# AT91.net
KiCad netlist of a schematic drawn in Altium Designer
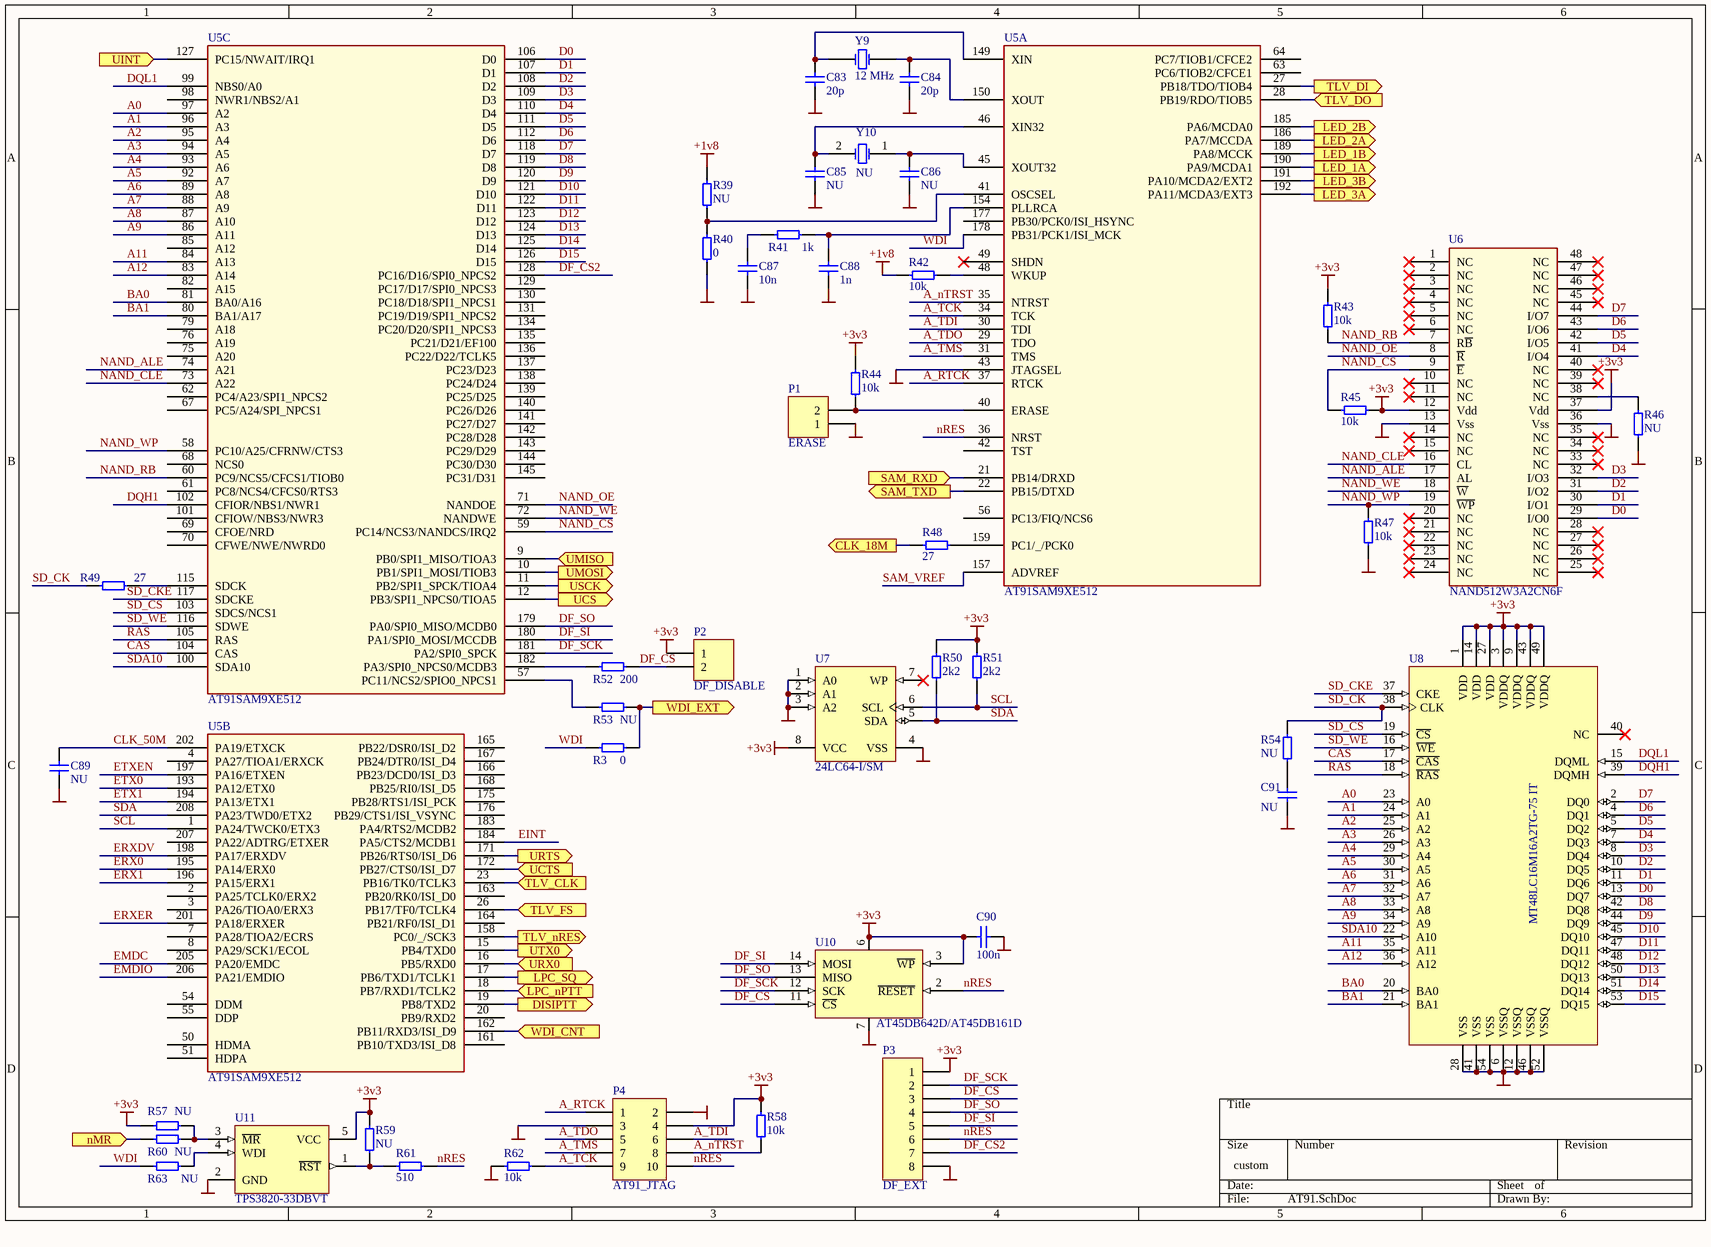
[diagram p0: AT91.SchDoc]

(export (version "E")
  (design (tool "Eeschema 10.0.6"))
  (components
    (comp (ref "C83")
      (value "20p")
      (footprint "CAPC1608L")
      (description "Capacitor")
      (fields (field (name "PUBLISHER") "Altium Limited"))
      (libsource (lib "Sch components") (part "Cap"))
    )
    (comp (ref "C84")
      (value "20p")
      (footprint "CAPC1608L")
      (description "Capacitor")
      (fields (field (name "PUBLISHER") "Altium Limited"))
      (libsource (lib "Sch components") (part "Cap"))
    )
    (comp (ref "C85")
      (value "NU")
      (footprint "CAPC1608L")
      (description "Capacitor")
      (fields (field (name "PUBLISHER") "Altium Limited"))
      (libsource (lib "Sch components") (part "Cap"))
    )
    (comp (ref "C86")
      (value "NU")
      (footprint "CAPC1608L")
      (description "Capacitor")
      (fields (field (name "PUBLISHER") "Altium Limited"))
      (libsource (lib "Sch components") (part "Cap"))
    )
    (comp (ref "C87")
      (value "10n")
      (footprint "CAPC1608L")
      (description "Capacitor")
      (fields (field (name "PUBLISHER") "Altium Limited"))
      (libsource (lib "Sch components") (part "Cap"))
    )
    (comp (ref "C88")
      (value "1n")
      (footprint "CAPC1608L")
      (description "Capacitor")
      (fields (field (name "PUBLISHER") "Altium Limited"))
      (libsource (lib "Sch components") (part "Cap"))
    )
    (comp (ref "C89")
      (value "NU")
      (footprint "CAPC1608L")
      (description "Capacitor")
      (fields (field (name "PUBLISHER") "Altium Limited"))
      (libsource (lib "Sch components") (part "Cap"))
    )
    (comp (ref "C90")
      (value "100n")
      (footprint "CAPC1608N")
      (description "Capacitor")
      (fields (field (name "PUBLISHER") "Altium Limited"))
      (libsource (lib "") (part "Cap_1"))
    )
    (comp (ref "C91")
      (value "NU")
      (footprint "CAPC1608L")
      (description "Capacitor")
      (fields (field (name "PUBLISHER") "Altium Limited"))
      (libsource (lib "Sch components") (part "Cap"))
    )
    (comp (ref "P1")
      (value "ERASE")
      (footprint "HDR1X2")
      (description "Header, 2-Pin")
      (fields (field (name "PUBLISHER") "Altium Limited"))
      (libsource (lib "") (part "Header 2_1"))
    )
    (comp (ref "P2")
      (value "DF_DISABLE")
      (footprint "HDR1X2")
      (description "Header, 2-Pin")
      (fields (field (name "PUBLISHER") "Altium Limited"))
      (libsource (lib "Miscellaneous Connectors") (part "Header 2"))
    )
    (comp (ref "P3")
      (value "DF_EXT")
      (footprint "HDR1X8")
      (description "Header, 8-Pin")
      (fields (field (name "PUBLISHER") "Altium Limited"))
      (libsource (lib "Miscellaneous Connectors") (part "Header 8"))
    )
    (comp (ref "P4")
      (value "AT91_JTAG")
      (footprint "HDR2X5")
      (description "Header, 5-Pin, Dual row")
      (fields (field (name "PUBLISHER") "Altium Limited"))
      (libsource (lib "Miscellaneous Connectors") (part "Header 5X2"))
    )
    (comp (ref "R3")
      (value "0")
      (footprint "RESC1608L")
      (description "Resistor")
      (fields (field (name "PUBLISHER") "Altium Limited"))
      (libsource (lib "Sch components") (part "Res"))
    )
    (comp (ref "R39")
      (value "NU")
      (footprint "RESC1608L")
      (description "Resistor")
      (fields (field (name "PUBLISHER") "Altium Limited"))
      (libsource (lib "Sch components") (part "Res"))
    )
    (comp (ref "R40")
      (value "0")
      (footprint "RESC1608L")
      (description "Resistor")
      (fields (field (name "PUBLISHER") "Altium Limited"))
      (libsource (lib "Sch components") (part "Res"))
    )
    (comp (ref "R41")
      (value "1k")
      (footprint "RESC1608L")
      (description "Resistor")
      (fields (field (name "PUBLISHER") "Altium Limited"))
      (libsource (lib "Sch components") (part "Res"))
    )
    (comp (ref "R42")
      (value "10k")
      (footprint "RESC1608L")
      (description "Resistor")
      (fields (field (name "PUBLISHER") "Altium Limited"))
      (libsource (lib "Sch components") (part "Res"))
    )
    (comp (ref "R43")
      (value "10k")
      (footprint "RESC1608L")
      (description "Resistor")
      (fields (field (name "PUBLISHER") "Altium Limited"))
      (libsource (lib "Sch components") (part "Res"))
    )
    (comp (ref "R44")
      (value "10k")
      (footprint "RESC1608L")
      (description "Resistor")
      (fields (field (name "PUBLISHER") "Altium Limited"))
      (libsource (lib "Sch components") (part "Res"))
    )
    (comp (ref "R45")
      (value "10k")
      (footprint "RESC1608L")
      (description "Resistor")
      (fields (field (name "PUBLISHER") "Altium Limited"))
      (libsource (lib "Sch components") (part "Res"))
    )
    (comp (ref "R46")
      (value "NU")
      (footprint "RESC1608L")
      (description "Resistor")
      (fields (field (name "PUBLISHER") "Altium Limited"))
      (libsource (lib "Sch components") (part "Res"))
    )
    (comp (ref "R47")
      (value "10k")
      (footprint "RESC1608L")
      (description "Resistor")
      (fields (field (name "PUBLISHER") "Altium Limited"))
      (libsource (lib "Sch components") (part "Res"))
    )
    (comp (ref "R48")
      (value "27")
      (footprint "RESC1608L")
      (description "Resistor")
      (fields (field (name "PUBLISHER") "Altium Limited"))
      (libsource (lib "Sch components") (part "Res"))
    )
    (comp (ref "R49")
      (value "27")
      (footprint "RESC1608L")
      (description "Resistor")
      (fields (field (name "PUBLISHER") "Altium Limited"))
      (libsource (lib "Sch components") (part "Res"))
    )
    (comp (ref "R50")
      (value "2k2")
      (footprint "RESC1608L")
      (description "Resistor")
      (fields (field (name "PUBLISHER") "Altium Limited"))
      (libsource (lib "Sch components") (part "Res"))
    )
    (comp (ref "R51")
      (value "2k2")
      (footprint "RESC1608L")
      (description "Resistor")
      (fields (field (name "PUBLISHER") "Altium Limited"))
      (libsource (lib "Sch components") (part "Res"))
    )
    (comp (ref "R52")
      (value "200")
      (footprint "RESC1608L")
      (description "Resistor")
      (fields (field (name "PUBLISHER") "Altium Limited"))
      (libsource (lib "Sch components") (part "Res"))
    )
    (comp (ref "R53")
      (value "NU")
      (footprint "RESC1608L")
      (description "Resistor")
      (fields (field (name "PUBLISHER") "Altium Limited"))
      (libsource (lib "Sch components") (part "Res"))
    )
    (comp (ref "R54")
      (value "NU")
      (footprint "RESC1608L")
      (description "Resistor")
      (fields (field (name "PUBLISHER") "Altium Limited"))
      (libsource (lib "Sch components") (part "Res"))
    )
    (comp (ref "R57")
      (value "NU")
      (footprint "RESC1608L")
      (description "Resistor")
      (fields (field (name "PUBLISHER") "Altium Limited"))
      (libsource (lib "Sch components") (part "Res"))
    )
    (comp (ref "R58")
      (value "10k")
      (footprint "RESC1608L")
      (description "Resistor")
      (fields (field (name "PUBLISHER") "Altium Limited"))
      (libsource (lib "Sch components") (part "Res"))
    )
    (comp (ref "R59")
      (value "NU")
      (footprint "RESC1608L")
      (description "Resistor")
      (fields (field (name "PUBLISHER") "Altium Limited"))
      (libsource (lib "Sch components") (part "Res"))
    )
    (comp (ref "R60")
      (value "NU")
      (footprint "RESC1608L")
      (description "Resistor")
      (fields (field (name "PUBLISHER") "Altium Limited"))
      (libsource (lib "Sch components") (part "Res"))
    )
    (comp (ref "R61")
      (value "510")
      (footprint "RESC1608L")
      (description "Resistor")
      (fields (field (name "PUBLISHER") "Altium Limited"))
      (libsource (lib "Sch components") (part "Res"))
    )
    (comp (ref "R62")
      (value "10k")
      (footprint "RESC1608L")
      (description "Resistor")
      (fields (field (name "PUBLISHER") "Altium Limited"))
      (libsource (lib "Sch components") (part "Res"))
    )
    (comp (ref "R63")
      (value "NU")
      (footprint "RESC1608L")
      (description "Resistor")
      (fields (field (name "PUBLISHER") "Altium Limited"))
      (libsource (lib "Sch components") (part "Res"))
    )
    (comp (ref "U5")
      (value "AT91SAM9XE512")
      (footprint "SQFP50P3120X3120-208N")
      (libsource (lib "MyWLib") (part "AT91SAM9XE512"))
    )
    (comp (ref "U6")
      (value "NAND512W3A2CN6F")
      (footprint "TSSOP50P2000-48AN")
      (description "256Mbit 528B/264 Word Page , 1.8/3V NAND Flash(x8)")
      (libsource (lib "MyWLib") (part "NAND256W3A2BN6E"))
    )
    (comp (ref "U7")
      (value "24LC64-I/SM")
      (footprint "SOIJ-SM8_L")
      (description "128Kbit, 400kHz, 2.5V, I2C Serial EEPROM, 8-Pin SOIC 208mil, Industrial Temperature")
      (fields (field (name "PUBLISHER") "Altium Limited"))
      (libsource (lib "Microchip EEPROM I2C Serial") (part "24LC128-I/SM"))
    )
    (comp (ref "U8")
      (value "MT48LC16M16A2TG-75 IT")
      (footprint "SOP80P1176-54N")
      (description "256Mb Synchronous High-Speed CMOS DRAM, 16Mb x 16Bit x 4 Banks, 54-Pin TSOP, Industrial")
      (fields (field (name "PUBLISHER") "Altium Limited"))
      (libsource (lib "Micron Memory Dynamic RAM") (part "MT48LC16M16A2TG-75 IT"))
    )
    (comp (ref "U10")
      (value "AT45DB642D/AT45DB161D")
      (footprint "TSSOP55P1340-28BN")
      (description "64 Mb 2.5/2.7 V DataFlash")
      (libsource (lib "Sch components") (part "AT45DB642D"))
    )
    (comp (ref "U11")
      (value "TPS3820-33DBVT")
      (footprint "SOT23-5")
      (description "5-Pin Microprocessor Supervisory Circuit")
      (fields (field (name "PUBLISHER") "Altium Limited"))
      (libsource (lib "Maxim Power Mgt Supervisory Circuit") (part "MAX823LEUK"))
    )
    (comp (ref "Y9")
      (value "12 MHz")
      (footprint "HC49/S")
      (description "Crystal Oscillator")
      (fields (field (name "PUBLISHER") "Altium Limited"))
      (libsource (lib "Sch components") (part "XTAL"))
    )
    (comp (ref "Y10")
      (value "NU")
      (footprint "R38")
      (description "Crystal Oscillator")
      (fields (field (name "PUBLISHER") "Altium Limited"))
      (libsource (lib "Miscellaneous Devices") (part "XTAL"))
    )
  )
  (nets
    (net (code "1") (name "+1v8") (class "Default")
      (node (ref "R39") (pin "2") (pinfunction "2_2") (pintype "passive"))
      (node (ref "R42") (pin "2") (pinfunction "2_2") (pintype "passive"))
    )
    (net (code "2") (name "+3v3") (class "Default")
      (node (ref "C90") (pin "2") (pinfunction "2_2") (pintype "passive"))
      (node (ref "P2") (pin "1") (pinfunction "1_1") (pintype "passive"))
      (node (ref "P3") (pin "1") (pinfunction "1_1") (pintype "passive"))
      (node (ref "P4") (pin "4") (pinfunction "4_4") (pintype "passive"))
      (node (ref "R43") (pin "2") (pinfunction "2_2") (pintype "passive"))
      (node (ref "R44") (pin "2") (pinfunction "2_2") (pintype "passive"))
      (node (ref "R45") (pin "1") (pinfunction "1_1") (pintype "passive"))
      (node (ref "R50") (pin "2") (pinfunction "2_2") (pintype "passive"))
      (node (ref "R51") (pin "2") (pinfunction "2_2") (pintype "passive"))
      (node (ref "R57") (pin "1") (pinfunction "1_1") (pintype "passive"))
      (node (ref "R58") (pin "2") (pinfunction "2_2") (pintype "passive"))
      (node (ref "R59") (pin "2") (pinfunction "2_2") (pintype "passive"))
      (node (ref "U10") (pin "3") (pinfunction "~{WP}_3") (pintype "input"))
      (node (ref "U10") (pin "6") (pinfunction "VCC_6") (pintype "power_in"))
      (node (ref "U11") (pin "5") (pinfunction "VCC_5") (pintype "power_in"))
      (node (ref "U6") (pin "12") (pinfunction "Vdd_12") (pintype "passive"))
      (node (ref "U6") (pin "37") (pinfunction "Vdd_37") (pintype "passive"))
      (node (ref "U7") (pin "8") (pinfunction "VCC_8") (pintype "power_in"))
      (node (ref "U8") (pin "1") (pinfunction "VDD_1") (pintype "power_in"))
      (node (ref "U8") (pin "14") (pinfunction "VDD_14") (pintype "power_in"))
      (node (ref "U8") (pin "27") (pinfunction "VDD_27") (pintype "power_in"))
      (node (ref "U8") (pin "3") (pinfunction "VDDQ_3") (pintype "power_in"))
      (node (ref "U8") (pin "43") (pinfunction "VDDQ_43") (pintype "power_in"))
      (node (ref "U8") (pin "49") (pinfunction "VDDQ_49") (pintype "power_in"))
      (node (ref "U8") (pin "9") (pinfunction "VDDQ_9") (pintype "power_in"))
    )
    (net (code "3") (name "/A0") (class "Default")
      (node (ref "U5") (pin "97") (pinfunction "A2_97") (pintype "passive"))
      (node (ref "U8") (pin "23") (pinfunction "A0_23") (pintype "input"))
    )
    (net (code "4") (name "/A1") (class "Default")
      (node (ref "U5") (pin "96") (pinfunction "A3_96") (pintype "passive"))
      (node (ref "U8") (pin "24") (pinfunction "A1_24") (pintype "input"))
    )
    (net (code "5") (name "/A2") (class "Default")
      (node (ref "U5") (pin "95") (pinfunction "A4_95") (pintype "passive"))
      (node (ref "U8") (pin "25") (pinfunction "A2_25") (pintype "input"))
    )
    (net (code "6") (name "/A3") (class "Default")
      (node (ref "U5") (pin "94") (pinfunction "A5_94") (pintype "passive"))
      (node (ref "U8") (pin "26") (pinfunction "A3_26") (pintype "input"))
    )
    (net (code "7") (name "/A4") (class "Default")
      (node (ref "U5") (pin "93") (pinfunction "A6_93") (pintype "passive"))
      (node (ref "U8") (pin "29") (pinfunction "A4_29") (pintype "input"))
    )
    (net (code "8") (name "/A5") (class "Default")
      (node (ref "U5") (pin "92") (pinfunction "A7_92") (pintype "passive"))
      (node (ref "U8") (pin "30") (pinfunction "A5_30") (pintype "input"))
    )
    (net (code "9") (name "/A6") (class "Default")
      (node (ref "U5") (pin "89") (pinfunction "A8_89") (pintype "passive"))
      (node (ref "U8") (pin "31") (pinfunction "A6_31") (pintype "input"))
    )
    (net (code "10") (name "/A7") (class "Default")
      (node (ref "U5") (pin "88") (pinfunction "A9_88") (pintype "passive"))
      (node (ref "U8") (pin "32") (pinfunction "A7_32") (pintype "input"))
    )
    (net (code "11") (name "/A8") (class "Default")
      (node (ref "U5") (pin "87") (pinfunction "A10_87") (pintype "passive"))
      (node (ref "U8") (pin "33") (pinfunction "A8_33") (pintype "input"))
    )
    (net (code "12") (name "/A9") (class "Default")
      (node (ref "U5") (pin "86") (pinfunction "A11_86") (pintype "passive"))
      (node (ref "U8") (pin "34") (pinfunction "A9_34") (pintype "input"))
    )
    (net (code "13") (name "/A11") (class "Default")
      (node (ref "U5") (pin "84") (pinfunction "A13_84") (pintype "passive"))
      (node (ref "U8") (pin "35") (pinfunction "A11_35") (pintype "input"))
    )
    (net (code "14") (name "/A12") (class "Default")
      (node (ref "U5") (pin "83") (pinfunction "A14_83") (pintype "passive"))
      (node (ref "U8") (pin "36") (pinfunction "A12_36") (pintype "input"))
    )
    (net (code "15") (name "/A_RTCK") (class "Default")
      (node (ref "P4") (pin "1") (pinfunction "1_1") (pintype "passive"))
      (node (ref "U5") (pin "37") (pinfunction "RTCK_37") (pintype "passive"))
    )
    (net (code "16") (name "/A_TCK") (class "Default")
      (node (ref "P4") (pin "9") (pinfunction "9_9") (pintype "passive"))
      (node (ref "R62") (pin "1") (pinfunction "1_1") (pintype "passive"))
      (node (ref "U5") (pin "34") (pinfunction "TCK_34") (pintype "passive"))
    )
    (net (code "17") (name "/A_TDI") (class "Default")
      (node (ref "P4") (pin "6") (pinfunction "6_6") (pintype "passive"))
      (node (ref "U5") (pin "30") (pinfunction "TDI_30") (pintype "passive"))
    )
    (net (code "18") (name "/A_TDO") (class "Default")
      (node (ref "P4") (pin "5") (pinfunction "5_5") (pintype "passive"))
      (node (ref "U5") (pin "29") (pinfunction "TDO_29") (pintype "passive"))
    )
    (net (code "19") (name "/A_TMS") (class "Default")
      (node (ref "P4") (pin "7") (pinfunction "7_7") (pintype "passive"))
      (node (ref "U5") (pin "31") (pinfunction "TMS_31") (pintype "passive"))
    )
    (net (code "20") (name "/A_nTRST") (class "Default")
      (node (ref "P4") (pin "8") (pinfunction "8_8") (pintype "passive"))
      (node (ref "R58") (pin "1") (pinfunction "1_1") (pintype "passive"))
      (node (ref "U5") (pin "35") (pinfunction "NTRST_35") (pintype "passive"))
    )
    (net (code "21") (name "/BA0") (class "Default")
      (node (ref "U5") (pin "81") (pinfunction "BA0/A16_81") (pintype "passive"))
      (node (ref "U8") (pin "20") (pinfunction "BA0_20") (pintype "input"))
    )
    (net (code "22") (name "/BA1") (class "Default")
      (node (ref "U5") (pin "80") (pinfunction "BA1/A17_80") (pintype "passive"))
      (node (ref "U8") (pin "21") (pinfunction "BA1_21") (pintype "input"))
    )
    (net (code "23") (name "/CAS") (class "Default")
      (node (ref "U5") (pin "104") (pinfunction "CAS_104") (pintype "passive"))
      (node (ref "U8") (pin "17") (pinfunction "~{CAS}_17") (pintype "input"))
    )
    (net (code "24") (name "/CLK_18M") (class "Default")
      (node (ref "R48") (pin "2") (pinfunction "2_2") (pintype "passive"))
    )
    (net (code "25") (name "/CLK_50M") (class "Default")
      (node (ref "C89") (pin "2") (pinfunction "2_2") (pintype "passive"))
      (node (ref "U5") (pin "202") (pinfunction "PA19/ETXCK_202") (pintype "passive"))
    )
    (net (code "26") (name "/D0") (class "Default")
      (node (ref "U5") (pin "106") (pinfunction "D0_106") (pintype "passive"))
      (node (ref "U6") (pin "29") (pinfunction "I/O0_29") (pintype "passive"))
      (node (ref "U8") (pin "13") (pinfunction "DQ7_13") (pintype "bidirectional"))
    )
    (net (code "27") (name "/D1") (class "Default")
      (node (ref "U5") (pin "107") (pinfunction "D1_107") (pintype "passive"))
      (node (ref "U6") (pin "30") (pinfunction "I/O1_30") (pintype "passive"))
      (node (ref "U8") (pin "11") (pinfunction "DQ6_11") (pintype "bidirectional"))
    )
    (net (code "28") (name "/D2") (class "Default")
      (node (ref "U5") (pin "108") (pinfunction "D2_108") (pintype "passive"))
      (node (ref "U6") (pin "31") (pinfunction "I/O2_31") (pintype "passive"))
      (node (ref "U8") (pin "10") (pinfunction "DQ5_10") (pintype "bidirectional"))
    )
    (net (code "29") (name "/D3") (class "Default")
      (node (ref "U5") (pin "109") (pinfunction "D3_109") (pintype "passive"))
      (node (ref "U6") (pin "32") (pinfunction "I/O3_32") (pintype "passive"))
      (node (ref "U8") (pin "8") (pinfunction "DQ4_8") (pintype "bidirectional"))
    )
    (net (code "30") (name "/D4") (class "Default")
      (node (ref "U5") (pin "110") (pinfunction "D4_110") (pintype "passive"))
      (node (ref "U6") (pin "41") (pinfunction "I/O4_41") (pintype "passive"))
      (node (ref "U8") (pin "7") (pinfunction "DQ3_7") (pintype "bidirectional"))
    )
    (net (code "31") (name "/D5") (class "Default")
      (node (ref "U5") (pin "111") (pinfunction "D5_111") (pintype "passive"))
      (node (ref "U6") (pin "42") (pinfunction "I/O5_42") (pintype "passive"))
      (node (ref "U8") (pin "5") (pinfunction "DQ2_5") (pintype "bidirectional"))
    )
    (net (code "32") (name "/D6") (class "Default")
      (node (ref "U5") (pin "112") (pinfunction "D6_112") (pintype "passive"))
      (node (ref "U6") (pin "43") (pinfunction "I/O6_43") (pintype "passive"))
      (node (ref "U8") (pin "4") (pinfunction "DQ1_4") (pintype "bidirectional"))
    )
    (net (code "33") (name "/D7") (class "Default")
      (node (ref "U5") (pin "118") (pinfunction "D7_118") (pintype "passive"))
      (node (ref "U6") (pin "44") (pinfunction "I/O7_44") (pintype "passive"))
      (node (ref "U8") (pin "2") (pinfunction "DQ0_2") (pintype "bidirectional"))
    )
    (net (code "34") (name "/D8") (class "Default")
      (node (ref "U5") (pin "119") (pinfunction "D8_119") (pintype "passive"))
      (node (ref "U8") (pin "42") (pinfunction "DQ8_42") (pintype "bidirectional"))
    )
    (net (code "35") (name "/D9") (class "Default")
      (node (ref "U5") (pin "120") (pinfunction "D9_120") (pintype "passive"))
      (node (ref "U8") (pin "44") (pinfunction "DQ9_44") (pintype "bidirectional"))
    )
    (net (code "36") (name "/D10") (class "Default")
      (node (ref "U5") (pin "121") (pinfunction "D10_121") (pintype "passive"))
      (node (ref "U8") (pin "45") (pinfunction "DQ10_45") (pintype "bidirectional"))
    )
    (net (code "37") (name "/D11") (class "Default")
      (node (ref "U5") (pin "122") (pinfunction "D11_122") (pintype "passive"))
      (node (ref "U8") (pin "47") (pinfunction "DQ11_47") (pintype "bidirectional"))
    )
    (net (code "38") (name "/D12") (class "Default")
      (node (ref "U5") (pin "123") (pinfunction "D12_123") (pintype "passive"))
      (node (ref "U8") (pin "48") (pinfunction "DQ12_48") (pintype "bidirectional"))
    )
    (net (code "39") (name "/D13") (class "Default")
      (node (ref "U5") (pin "124") (pinfunction "D13_124") (pintype "passive"))
      (node (ref "U8") (pin "50") (pinfunction "DQ13_50") (pintype "bidirectional"))
    )
    (net (code "40") (name "/D14") (class "Default")
      (node (ref "U5") (pin "125") (pinfunction "D14_125") (pintype "passive"))
      (node (ref "U8") (pin "51") (pinfunction "DQ14_51") (pintype "bidirectional"))
    )
    (net (code "41") (name "/D15") (class "Default")
      (node (ref "U5") (pin "126") (pinfunction "D15_126") (pintype "passive"))
      (node (ref "U8") (pin "53") (pinfunction "DQ15_53") (pintype "bidirectional"))
    )
    (net (code "42") (name "/DF_CS") (class "Default")
      (node (ref "P2") (pin "2") (pinfunction "2_2") (pintype "passive"))
      (node (ref "P3") (pin "3") (pinfunction "3_3") (pintype "passive"))
      (node (ref "R52") (pin "1") (pinfunction "1_1") (pintype "passive"))
      (node (ref "U10") (pin "11") (pinfunction "~{CS}_11") (pintype "input"))
    )
    (net (code "43") (name "/DF_CS2") (class "Default")
      (node (ref "P3") (pin "7") (pinfunction "7_7") (pintype "passive"))
      (node (ref "U5") (pin "128") (pinfunction "PC16/D16/SPI0_NPCS2_128") (pintype "passive"))
    )
    (net (code "44") (name "/DF_SCK") (class "Default")
      (node (ref "P3") (pin "2") (pinfunction "2_2") (pintype "passive"))
      (node (ref "U10") (pin "12") (pinfunction "SCK_12") (pintype "input"))
      (node (ref "U5") (pin "181") (pinfunction "PA2/SPI0_SPCK_181") (pintype "passive"))
    )
    (net (code "45") (name "/DF_SI") (class "Default")
      (node (ref "P3") (pin "5") (pinfunction "5_5") (pintype "passive"))
      (node (ref "U10") (pin "14") (pinfunction "MOSI_14") (pintype "input"))
      (node (ref "U5") (pin "180") (pinfunction "PA1/SPI0_MOSI/MCCDB_180") (pintype "passive"))
    )
    (net (code "46") (name "/DF_SO") (class "Default")
      (node (ref "P3") (pin "4") (pinfunction "4_4") (pintype "passive"))
      (node (ref "U10") (pin "13") (pinfunction "MISO_13") (pintype "tri_state"))
      (node (ref "U5") (pin "179") (pinfunction "PA0/SPI0_MISO/MCDB0_179") (pintype "passive"))
    )
    (net (code "47") (name "/DISIPTT") (class "Default")
      (node (ref "U5") (pin "19") (pinfunction "PB8/TXD2_19") (pintype "passive"))
    )
    (net (code "48") (name "/DQH1") (class "Default")
      (node (ref "U5") (pin "102") (pinfunction "CFIOR/NBS1/NWR1_102") (pintype "passive"))
      (node (ref "U8") (pin "39") (pinfunction "DQMH_39") (pintype "input"))
    )
    (net (code "49") (name "/DQL1") (class "Default")
      (node (ref "U5") (pin "99") (pinfunction "NBS0/A0_99") (pintype "passive"))
      (node (ref "U8") (pin "15") (pinfunction "DQML_15") (pintype "input"))
    )
    (net (code "50") (name "/EINT") (class "Default")
      (node (ref "U5") (pin "184") (pinfunction "PA5/CTS2/MCDB1_184") (pintype "passive"))
    )
    (net (code "51") (name "/EMDC") (class "Default")
      (node (ref "U5") (pin "205") (pinfunction "PA20/EMDC_205") (pintype "passive"))
    )
    (net (code "52") (name "/EMDIO") (class "Default")
      (node (ref "U5") (pin "206") (pinfunction "PA21/EMDIO_206") (pintype "passive"))
    )
    (net (code "53") (name "/ERX0") (class "Default")
      (node (ref "U5") (pin "195") (pinfunction "PA14/ERX0_195") (pintype "passive"))
    )
    (net (code "54") (name "/ERX1") (class "Default")
      (node (ref "U5") (pin "196") (pinfunction "PA15/ERX1_196") (pintype "passive"))
    )
    (net (code "55") (name "/ERXDV") (class "Default")
      (node (ref "U5") (pin "198") (pinfunction "PA17/ERXDV_198") (pintype "passive"))
    )
    (net (code "56") (name "/ERXER") (class "Default")
      (node (ref "U5") (pin "201") (pinfunction "PA18/ERXER_201") (pintype "passive"))
    )
    (net (code "57") (name "/ETX0") (class "Default")
      (node (ref "U5") (pin "193") (pinfunction "PA12/ETX0_193") (pintype "passive"))
    )
    (net (code "58") (name "/ETX1") (class "Default")
      (node (ref "U5") (pin "194") (pinfunction "PA13/ETX1_194") (pintype "passive"))
    )
    (net (code "59") (name "/ETXEN") (class "Default")
      (node (ref "U5") (pin "197") (pinfunction "PA16/ETXEN_197") (pintype "passive"))
    )
    (net (code "60") (name "/LED_1A") (class "Default")
      (node (ref "U5") (pin "190") (pinfunction "PA9/MCDA1_190") (pintype "passive"))
    )
    (net (code "61") (name "/LED_1B") (class "Default")
      (node (ref "U5") (pin "189") (pinfunction "PA8/MCCK_189") (pintype "passive"))
    )
    (net (code "62") (name "/LED_2A") (class "Default")
      (node (ref "U5") (pin "186") (pinfunction "PA7/MCCDA_186") (pintype "passive"))
    )
    (net (code "63") (name "/LED_2B") (class "Default")
      (node (ref "U5") (pin "185") (pinfunction "PA6/MCDA0_185") (pintype "passive"))
    )
    (net (code "64") (name "/LED_3A") (class "Default")
      (node (ref "U5") (pin "192") (pinfunction "PA11/MCDA3/EXT3_192") (pintype "passive"))
    )
    (net (code "65") (name "/LED_3B") (class "Default")
      (node (ref "U5") (pin "191") (pinfunction "PA10/MCDA2/EXT2_191") (pintype "passive"))
    )
    (net (code "66") (name "/LPC_SQ") (class "Default")
      (node (ref "U5") (pin "17") (pinfunction "PB6/TXD1/TCLK1_17") (pintype "passive"))
    )
    (net (code "67") (name "/LPC_nPTT") (class "Default")
      (node (ref "U5") (pin "18") (pinfunction "PB7/RXD1/TCLK2_18") (pintype "passive"))
    )
    (net (code "68") (name "/NAND_ALE") (class "Default")
      (node (ref "U5") (pin "74") (pinfunction "A21_74") (pintype "passive"))
      (node (ref "U6") (pin "17") (pinfunction "AL_17") (pintype "passive"))
    )
    (net (code "69") (name "/NAND_CLE") (class "Default")
      (node (ref "U5") (pin "73") (pinfunction "A22_73") (pintype "passive"))
      (node (ref "U6") (pin "16") (pinfunction "CL_16") (pintype "passive"))
    )
    (net (code "70") (name "/NAND_CS") (class "Default")
      (node (ref "R45") (pin "2") (pinfunction "2_2") (pintype "passive"))
      (node (ref "U5") (pin "59") (pinfunction "PC14/NCS3/NANDCS/IRQ2_59") (pintype "passive"))
      (node (ref "U6") (pin "9") (pinfunction "~{E}_9") (pintype "passive"))
    )
    (net (code "71") (name "/NAND_OE") (class "Default")
      (node (ref "U5") (pin "71") (pinfunction "NANDOE_71") (pintype "passive"))
      (node (ref "U6") (pin "8") (pinfunction "~{R}_8") (pintype "passive"))
    )
    (net (code "72") (name "/NAND_RB") (class "Default")
      (node (ref "R43") (pin "1") (pinfunction "1_1") (pintype "passive"))
      (node (ref "U5") (pin "60") (pinfunction "PC9/NCS5/CFCS1/TIOB0_60") (pintype "passive"))
      (node (ref "U6") (pin "7") (pinfunction "R~{B}_7") (pintype "passive"))
    )
    (net (code "73") (name "/NAND_WE") (class "Default")
      (node (ref "U5") (pin "72") (pinfunction "NANDWE_72") (pintype "passive"))
      (node (ref "U6") (pin "18") (pinfunction "~{W}_18") (pintype "passive"))
    )
    (net (code "74") (name "/NAND_WP") (class "Default")
      (node (ref "R47") (pin "2") (pinfunction "2_2") (pintype "passive"))
      (node (ref "U5") (pin "58") (pinfunction "PC10/A25/CFRNW/CTS3_58") (pintype "passive"))
      (node (ref "U6") (pin "19") (pinfunction "~{WP}_19") (pintype "passive"))
    )
    (net (code "75") (name "/RAS") (class "Default")
      (node (ref "U5") (pin "105") (pinfunction "RAS_105") (pintype "passive"))
      (node (ref "U8") (pin "18") (pinfunction "~{RAS}_18") (pintype "input"))
    )
    (net (code "76") (name "/SAM_RXD") (class "Default")
      (node (ref "U5") (pin "21") (pinfunction "PB14/DRXD_21") (pintype "passive"))
    )
    (net (code "77") (name "/SAM_TXD") (class "Default")
      (node (ref "U5") (pin "22") (pinfunction "PB15/DTXD_22") (pintype "passive"))
    )
    (net (code "78") (name "/SAM_VREF") (class "Default")
      (node (ref "U5") (pin "157") (pinfunction "ADVREF_157") (pintype "passive"))
    )
    (net (code "79") (name "/SCL") (class "Default")
      (node (ref "R51") (pin "1") (pinfunction "1_1") (pintype "passive"))
      (node (ref "U5") (pin "1") (pinfunction "PA24/TWCK0/ETX3_1") (pintype "passive"))
      (node (ref "U7") (pin "6") (pinfunction "SCL_6") (pintype "input"))
    )
    (net (code "80") (name "/SDA") (class "Default")
      (node (ref "R50") (pin "1") (pinfunction "1_1") (pintype "passive"))
      (node (ref "U5") (pin "208") (pinfunction "PA23/TWD0/ETX2_208") (pintype "passive"))
      (node (ref "U7") (pin "5") (pinfunction "SDA_5") (pintype "bidirectional"))
    )
    (net (code "81") (name "/SDA10") (class "Default")
      (node (ref "U5") (pin "100") (pinfunction "SDA10_100") (pintype "passive"))
      (node (ref "U8") (pin "22") (pinfunction "A10_22") (pintype "input"))
    )
    (net (code "82") (name "/SD_CK") (class "Default")
      (node (ref "R49") (pin "2") (pinfunction "2_2") (pintype "passive"))
      (node (ref "R54") (pin "2") (pinfunction "2_2") (pintype "passive"))
      (node (ref "U8") (pin "38") (pinfunction "CLK_38") (pintype "input"))
    )
    (net (code "83") (name "/SD_CKE") (class "Default")
      (node (ref "U5") (pin "117") (pinfunction "SDCKE_117") (pintype "passive"))
      (node (ref "U8") (pin "37") (pinfunction "CKE_37") (pintype "input"))
    )
    (net (code "84") (name "/SD_CS") (class "Default")
      (node (ref "U5") (pin "103") (pinfunction "SDCS/NCS1_103") (pintype "passive"))
      (node (ref "U8") (pin "19") (pinfunction "~{CS}_19") (pintype "input"))
    )
    (net (code "85") (name "/SD_WE") (class "Default")
      (node (ref "U5") (pin "116") (pinfunction "SDWE_116") (pintype "passive"))
      (node (ref "U8") (pin "16") (pinfunction "~{WE}_16") (pintype "input"))
    )
    (net (code "86") (name "/TLV_CLK") (class "Default")
      (node (ref "U5") (pin "23") (pinfunction "PB16/TK0/TCLK3_23") (pintype "passive"))
    )
    (net (code "87") (name "/TLV_DI") (class "Default")
      (node (ref "U5") (pin "27") (pinfunction "PB18/TDO/TIOB4_27") (pintype "passive"))
    )
    (net (code "88") (name "/TLV_DO") (class "Default")
      (node (ref "U5") (pin "28") (pinfunction "PB19/RDO/TIOB5_28") (pintype "passive"))
    )
    (net (code "89") (name "/TLV_FS") (class "Default")
      (node (ref "U5") (pin "26") (pinfunction "PB17/TF0/TCLK4_26") (pintype "passive"))
    )
    (net (code "90") (name "/TLV_nRES") (class "Default")
      (node (ref "U5") (pin "158") (pinfunction "PC0/_/SCK3_158") (pintype "passive"))
    )
    (net (code "91") (name "/UCS") (class "Default")
      (node (ref "U5") (pin "12") (pinfunction "PB3/SPI1_NPCS0/TIOA5_12") (pintype "passive"))
    )
    (net (code "92") (name "/UCTS") (class "Default")
      (node (ref "U5") (pin "172") (pinfunction "PB27/CTS0/ISI_D7_172") (pintype "passive"))
    )
    (net (code "93") (name "/UINT") (class "Default")
      (node (ref "U5") (pin "127") (pinfunction "PC15/NWAIT/IRQ1_127") (pintype "passive"))
    )
    (net (code "94") (name "/UMISO") (class "Default")
      (node (ref "U5") (pin "9") (pinfunction "PB0/SPI1_MISO/TIOA3_9") (pintype "passive"))
    )
    (net (code "95") (name "/UMOSI") (class "Default")
      (node (ref "U5") (pin "10") (pinfunction "PB1/SPI1_MOSI/TIOB3_10") (pintype "passive"))
    )
    (net (code "96") (name "/URTS") (class "Default")
      (node (ref "U5") (pin "171") (pinfunction "PB26/RTS0/ISI_D6_171") (pintype "passive"))
    )
    (net (code "97") (name "/URX0") (class "Default")
      (node (ref "U5") (pin "16") (pinfunction "PB5/RXD0_16") (pintype "passive"))
    )
    (net (code "98") (name "/USCK") (class "Default")
      (node (ref "U5") (pin "11") (pinfunction "PB2/SPI1_SPCK/TIOA4_11") (pintype "passive"))
    )
    (net (code "99") (name "/UTX0") (class "Default")
      (node (ref "U5") (pin "15") (pinfunction "PB4/TXD0_15") (pintype "passive"))
    )
    (net (code "100") (name "/WDI") (class "Default")
      (node (ref "R3") (pin "1") (pinfunction "1_1") (pintype "passive"))
      (node (ref "R63") (pin "2") (pinfunction "2_2") (pintype "passive"))
      (node (ref "U5") (pin "178") (pinfunction "PB31/PCK1/ISI_MCK_178") (pintype "passive"))
    )
    (net (code "101") (name "/WDI_CNT") (class "Default")
      (node (ref "U5") (pin "162") (pinfunction "PB11/RXD3/ISI_D9_162") (pintype "passive"))
    )
    (net (code "102") (name "/WDI_EXT") (class "Default")
      (node (ref "R3") (pin "2") (pinfunction "2_2") (pintype "passive"))
      (node (ref "R53") (pin "2") (pinfunction "2_2") (pintype "passive"))
    )
    (net (code "103") (name "/nMR") (class "Default")
      (node (ref "R60") (pin "1") (pinfunction "1_1") (pintype "passive"))
    )
    (net (code "104") (name "/nRES") (class "Default")
      (node (ref "P3") (pin "6") (pinfunction "6_6") (pintype "passive"))
      (node (ref "P4") (pin "10") (pinfunction "10_10") (pintype "passive"))
      (node (ref "R61") (pin "1") (pinfunction "1_1") (pintype "passive"))
      (node (ref "U10") (pin "2") (pinfunction "~{RESET}_2") (pintype "input"))
      (node (ref "U5") (pin "36") (pinfunction "NRST_36") (pintype "passive"))
    )
    (net (code "105") (name "GND") (class "Default")
      (node (ref "C83") (pin "2") (pinfunction "2_2") (pintype "passive"))
      (node (ref "C84") (pin "2") (pinfunction "2_2") (pintype "passive"))
      (node (ref "C85") (pin "2") (pinfunction "2_2") (pintype "passive"))
      (node (ref "C86") (pin "2") (pinfunction "2_2") (pintype "passive"))
      (node (ref "C87") (pin "2") (pinfunction "2_2") (pintype "passive"))
      (node (ref "C88") (pin "2") (pinfunction "2_2") (pintype "passive"))
      (node (ref "C89") (pin "1") (pinfunction "1_1") (pintype "passive"))
      (node (ref "C90") (pin "1") (pinfunction "1_1") (pintype "passive"))
      (node (ref "C91") (pin "1") (pinfunction "1_1") (pintype "passive"))
      (node (ref "P1") (pin "1") (pinfunction "1_1") (pintype "passive"))
      (node (ref "P3") (pin "8") (pinfunction "8_8") (pintype "passive"))
      (node (ref "P4") (pin "2") (pinfunction "2_2") (pintype "passive"))
      (node (ref "P4") (pin "3") (pinfunction "3_3") (pintype "passive"))
      (node (ref "R40") (pin "1") (pinfunction "1_1") (pintype "passive"))
      (node (ref "R46") (pin "2") (pinfunction "2_2") (pintype "passive"))
      (node (ref "R47") (pin "1") (pinfunction "1_1") (pintype "passive"))
      (node (ref "R62") (pin "2") (pinfunction "2_2") (pintype "passive"))
      (node (ref "U10") (pin "7") (pinfunction "GND_7") (pintype "power_in"))
      (node (ref "U11") (pin "2") (pinfunction "GND_2") (pintype "power_in"))
      (node (ref "U5") (pin "43") (pinfunction "JTAGSEL_43") (pintype "passive"))
      (node (ref "U6") (pin "13") (pinfunction "Vss_13") (pintype "passive"))
      (node (ref "U6") (pin "36") (pinfunction "Vss_36") (pintype "passive"))
      (node (ref "U7") (pin "1") (pinfunction "A0_1") (pintype "input"))
      (node (ref "U7") (pin "2") (pinfunction "A1_2") (pintype "input"))
      (node (ref "U7") (pin "3") (pinfunction "A2_3") (pintype "input"))
      (node (ref "U7") (pin "4") (pinfunction "VSS_4") (pintype "power_in"))
      (node (ref "U8") (pin "12") (pinfunction "VSSQ_12") (pintype "power_in"))
      (node (ref "U8") (pin "28") (pinfunction "VSS_28") (pintype "power_in"))
      (node (ref "U8") (pin "41") (pinfunction "VSS_41") (pintype "power_in"))
      (node (ref "U8") (pin "46") (pinfunction "VSSQ_46") (pintype "power_in"))
      (node (ref "U8") (pin "52") (pinfunction "VSSQ_52") (pintype "power_in"))
      (node (ref "U8") (pin "54") (pinfunction "VSS_54") (pintype "power_in"))
      (node (ref "U8") (pin "6") (pinfunction "VSSQ_6") (pintype "power_in"))
    )
    (net (code "106") (name "Net-(C87-Pad1)") (class "Default")
      (node (ref "C87") (pin "1") (pinfunction "1_1") (pintype "passive"))
      (node (ref "R41") (pin "2") (pinfunction "2_2") (pintype "passive"))
    )
    (net (code "107") (name "Net-(C91-Pad2)") (class "Default")
      (node (ref "C91") (pin "2") (pinfunction "2_2") (pintype "passive"))
      (node (ref "R54") (pin "1") (pinfunction "1_1") (pintype "passive"))
    )
    (net (code "108") (name "Net-(R46-Pad1)") (class "Default")
      (node (ref "R46") (pin "1") (pinfunction "1_1") (pintype "passive"))
      (node (ref "U6") (pin "38") (pinfunction "NC_38") (pintype "passive"))
    )
    (net (code "109") (name "Net-(U5A-ERASE)") (class "Default")
      (node (ref "P1") (pin "2") (pinfunction "2_2") (pintype "passive"))
      (node (ref "R44") (pin "1") (pinfunction "1_1") (pintype "passive"))
      (node (ref "U5") (pin "40") (pinfunction "ERASE_40") (pintype "passive"))
    )
    (net (code "110") (name "Net-(U5A-OSCSEL)") (class "Default")
      (node (ref "R39") (pin "1") (pinfunction "1_1") (pintype "passive"))
      (node (ref "R40") (pin "2") (pinfunction "2_2") (pintype "passive"))
      (node (ref "U5") (pin "41") (pinfunction "OSCSEL_41") (pintype "passive"))
    )
    (net (code "111") (name "Net-(U5A-PC1{slash}_{slash}PCK0)") (class "Default")
      (node (ref "R48") (pin "1") (pinfunction "1_1") (pintype "passive"))
      (node (ref "U5") (pin "159") (pinfunction "PC1/_/PCK0_159") (pintype "passive"))
    )
    (net (code "112") (name "Net-(U5A-PLLRCA)") (class "Default")
      (node (ref "C88") (pin "1") (pinfunction "1_1") (pintype "passive"))
      (node (ref "R41") (pin "1") (pinfunction "1_1") (pintype "passive"))
      (node (ref "U5") (pin "154") (pinfunction "PLLRCA_154") (pintype "passive"))
    )
    (net (code "113") (name "Net-(U5A-WKUP)") (class "Default")
      (node (ref "R42") (pin "1") (pinfunction "1_1") (pintype "passive"))
      (node (ref "U5") (pin "48") (pinfunction "WKUP_48") (pintype "passive"))
    )
    (net (code "114") (name "Net-(U5A-XIN)") (class "Default")
      (node (ref "C83") (pin "1") (pinfunction "1_1") (pintype "passive"))
      (node (ref "U5") (pin "149") (pinfunction "XIN_149") (pintype "passive"))
      (node (ref "Y9") (pin "1") (pinfunction "OSC1_1") (pintype "passive"))
    )
    (net (code "115") (name "Net-(U5A-XIN32)") (class "Default")
      (node (ref "C85") (pin "1") (pinfunction "1_1") (pintype "passive"))
      (node (ref "U5") (pin "46") (pinfunction "XIN32_46") (pintype "passive"))
      (node (ref "Y10") (pin "2") (pinfunction "OSC2_2") (pintype "passive"))
    )
    (net (code "116") (name "Net-(U5A-XOUT)") (class "Default")
      (node (ref "C84") (pin "1") (pinfunction "1_1") (pintype "passive"))
      (node (ref "U5") (pin "150") (pinfunction "XOUT_150") (pintype "passive"))
      (node (ref "Y9") (pin "2") (pinfunction "OSC2_2") (pintype "passive"))
    )
    (net (code "117") (name "Net-(U5A-XOUT32)") (class "Default")
      (node (ref "C86") (pin "1") (pinfunction "1_1") (pintype "passive"))
      (node (ref "U5") (pin "45") (pinfunction "XOUT32_45") (pintype "passive"))
      (node (ref "Y10") (pin "1") (pinfunction "OSC1_1") (pintype "passive"))
    )
    (net (code "118") (name "Net-(U5C-PA3{slash}SPI0_NPCS0{slash}MCDB3)") (class "Default")
      (node (ref "R52") (pin "2") (pinfunction "2_2") (pintype "passive"))
      (node (ref "U5") (pin "182") (pinfunction "PA3/SPI0_NPCS0/MCDB3_182") (pintype "passive"))
    )
    (net (code "119") (name "Net-(U5C-PC11{slash}NCS2{slash}SPIO0_NPCS1)") (class "Default")
      (node (ref "R53") (pin "1") (pinfunction "1_1") (pintype "passive"))
      (node (ref "U5") (pin "57") (pinfunction "PC11/NCS2/SPIO0_NPCS1_57") (pintype "passive"))
    )
    (net (code "120") (name "Net-(U5C-SDCK)") (class "Default")
      (node (ref "R49") (pin "1") (pinfunction "1_1") (pintype "passive"))
      (node (ref "U5") (pin "115") (pinfunction "SDCK_115") (pintype "passive"))
    )
    (net (code "121") (name "Net-(U11-WDI)") (class "Default")
      (node (ref "R63") (pin "1") (pinfunction "1_1") (pintype "passive"))
      (node (ref "U11") (pin "4") (pinfunction "WDI_4") (pintype "input"))
    )
    (net (code "122") (name "Net-(U11-~{MR})") (class "Default")
      (node (ref "R57") (pin "2") (pinfunction "2_2") (pintype "passive"))
      (node (ref "R60") (pin "2") (pinfunction "2_2") (pintype "passive"))
      (node (ref "U11") (pin "3") (pinfunction "~{MR}_3") (pintype "input"))
    )
    (net (code "123") (name "Net-(U11-~{RST})") (class "Default")
      (node (ref "R59") (pin "1") (pinfunction "1_1") (pintype "passive"))
      (node (ref "R61") (pin "2") (pinfunction "2_2") (pintype "passive"))
      (node (ref "U11") (pin "1") (pinfunction "~{RST}_1") (pintype "output"))
    )
    (net (code "124") (name "unconnected-(U5A-PB30{slash}PCK0{slash}ISI_HSYNC-Pad177)") (class "Default")
      (node (ref "U5") (pin "177") (pinfunction "PB30/PCK0/ISI_HSYNC_177") (pintype "passive"))
    )
    (net (code "125") (name "unconnected-(U5A-PC6{slash}TIOB2{slash}CFCE1-Pad63)") (class "Default")
      (node (ref "U5") (pin "63") (pinfunction "PC6/TIOB2/CFCE1_63") (pintype "passive"))
    )
    (net (code "126") (name "unconnected-(U5A-PC7{slash}TIOB1{slash}CFCE2-Pad64)") (class "Default")
      (node (ref "U5") (pin "64") (pinfunction "PC7/TIOB1/CFCE2_64") (pintype "passive"))
    )
    (net (code "127") (name "unconnected-(U5A-PC13{slash}FIQ{slash}NCS6-Pad56)") (class "Default")
      (node (ref "U5") (pin "56") (pinfunction "PC13/FIQ/NCS6_56") (pintype "passive"))
    )
    (net (code "128") (name "unconnected-(U5A-SHDN-Pad49)") (class "Default")
      (node (ref "U5") (pin "49") (pinfunction "SHDN_49") (pintype "passive+no_connect"))
    )
    (net (code "129") (name "unconnected-(U5A-TST-Pad42)") (class "Default")
      (node (ref "U5") (pin "42") (pinfunction "TST_42") (pintype "passive"))
    )
    (net (code "130") (name "unconnected-(U5B-DDM-Pad54)") (class "Default")
      (node (ref "U5") (pin "54") (pinfunction "DDM_54") (pintype "passive"))
    )
    (net (code "131") (name "unconnected-(U5B-DDP-Pad55)") (class "Default")
      (node (ref "U5") (pin "55") (pinfunction "DDP_55") (pintype "passive"))
    )
    (net (code "132") (name "unconnected-(U5B-HDMA-Pad50)") (class "Default")
      (node (ref "U5") (pin "50") (pinfunction "HDMA_50") (pintype "passive"))
    )
    (net (code "133") (name "unconnected-(U5B-HDPA-Pad51)") (class "Default")
      (node (ref "U5") (pin "51") (pinfunction "HDPA_51") (pintype "passive"))
    )
    (net (code "134") (name "unconnected-(U5B-PA4{slash}RTS2{slash}MCDB2-Pad183)") (class "Default")
      (node (ref "U5") (pin "183") (pinfunction "PA4/RTS2/MCDB2_183") (pintype "passive"))
    )
    (net (code "135") (name "unconnected-(U5B-PA22{slash}ADTRG{slash}ETXER-Pad207)") (class "Default")
      (node (ref "U5") (pin "207") (pinfunction "PA22/ADTRG/ETXER_207") (pintype "passive"))
    )
    (net (code "136") (name "unconnected-(U5B-PA25{slash}TCLK0{slash}ERX2-Pad2)") (class "Default")
      (node (ref "U5") (pin "2") (pinfunction "PA25/TCLK0/ERX2_2") (pintype "passive"))
    )
    (net (code "137") (name "unconnected-(U5B-PA26{slash}TIOA0{slash}ERX3-Pad3)") (class "Default")
      (node (ref "U5") (pin "3") (pinfunction "PA26/TIOA0/ERX3_3") (pintype "passive"))
    )
    (net (code "138") (name "unconnected-(U5B-PA27{slash}TIOA1{slash}ERXCK-Pad4)") (class "Default")
      (node (ref "U5") (pin "4") (pinfunction "PA27/TIOA1/ERXCK_4") (pintype "passive"))
    )
    (net (code "139") (name "unconnected-(U5B-PA28{slash}TIOA2{slash}ECRS-Pad7)") (class "Default")
      (node (ref "U5") (pin "7") (pinfunction "PA28/TIOA2/ECRS_7") (pintype "passive"))
    )
    (net (code "140") (name "unconnected-(U5B-PA29{slash}SCK1{slash}ECOL-Pad8)") (class "Default")
      (node (ref "U5") (pin "8") (pinfunction "PA29/SCK1/ECOL_8") (pintype "passive"))
    )
    (net (code "141") (name "unconnected-(U5B-PB9{slash}RXD2-Pad20)") (class "Default")
      (node (ref "U5") (pin "20") (pinfunction "PB9/RXD2_20") (pintype "passive"))
    )
    (net (code "142") (name "unconnected-(U5B-PB10{slash}TXD3{slash}ISI_D8-Pad161)") (class "Default")
      (node (ref "U5") (pin "161") (pinfunction "PB10/TXD3/ISI_D8_161") (pintype "passive"))
    )
    (net (code "143") (name "unconnected-(U5B-PB20{slash}RK0{slash}ISI_D0-Pad163)") (class "Default")
      (node (ref "U5") (pin "163") (pinfunction "PB20/RK0/ISI_D0_163") (pintype "passive"))
    )
    (net (code "144") (name "unconnected-(U5B-PB21{slash}RF0{slash}ISI_D1-Pad164)") (class "Default")
      (node (ref "U5") (pin "164") (pinfunction "PB21/RF0/ISI_D1_164") (pintype "passive"))
    )
    (net (code "145") (name "unconnected-(U5B-PB22{slash}DSR0{slash}ISI_D2-Pad165)") (class "Default")
      (node (ref "U5") (pin "165") (pinfunction "PB22/DSR0/ISI_D2_165") (pintype "passive"))
    )
    (net (code "146") (name "unconnected-(U5B-PB23{slash}DCD0{slash}ISI_D3-Pad166)") (class "Default")
      (node (ref "U5") (pin "166") (pinfunction "PB23/DCD0/ISI_D3_166") (pintype "passive"))
    )
    (net (code "147") (name "unconnected-(U5B-PB24{slash}DTR0{slash}ISI_D4-Pad167)") (class "Default")
      (node (ref "U5") (pin "167") (pinfunction "PB24/DTR0/ISI_D4_167") (pintype "passive"))
    )
    (net (code "148") (name "unconnected-(U5B-PB25{slash}RI0{slash}ISI_D5-Pad168)") (class "Default")
      (node (ref "U5") (pin "168") (pinfunction "PB25/RI0/ISI_D5_168") (pintype "passive"))
    )
    (net (code "149") (name "unconnected-(U5B-PB28{slash}RTS1{slash}ISI_PCK-Pad175)") (class "Default")
      (node (ref "U5") (pin "175") (pinfunction "PB28/RTS1/ISI_PCK_175") (pintype "passive"))
    )
    (net (code "150") (name "unconnected-(U5B-PB29{slash}CTS1{slash}ISI_VSYNC-Pad176)") (class "Default")
      (node (ref "U5") (pin "176") (pinfunction "PB29/CTS1/ISI_VSYNC_176") (pintype "passive"))
    )
    (net (code "151") (name "unconnected-(U5C-A12-Pad85)") (class "Default")
      (node (ref "U5") (pin "85") (pinfunction "A12_85") (pintype "passive"))
    )
    (net (code "152") (name "unconnected-(U5C-A15-Pad82)") (class "Default")
      (node (ref "U5") (pin "82") (pinfunction "A15_82") (pintype "passive"))
    )
    (net (code "153") (name "unconnected-(U5C-A18-Pad79)") (class "Default")
      (node (ref "U5") (pin "79") (pinfunction "A18_79") (pintype "passive"))
    )
    (net (code "154") (name "unconnected-(U5C-A19-Pad76)") (class "Default")
      (node (ref "U5") (pin "76") (pinfunction "A19_76") (pintype "passive"))
    )
    (net (code "155") (name "unconnected-(U5C-A20-Pad75)") (class "Default")
      (node (ref "U5") (pin "75") (pinfunction "A20_75") (pintype "passive"))
    )
    (net (code "156") (name "unconnected-(U5C-CFIOW{slash}NBS3{slash}NWR3-Pad101)") (class "Default")
      (node (ref "U5") (pin "101") (pinfunction "CFIOW/NBS3/NWR3_101") (pintype "passive"))
    )
    (net (code "157") (name "unconnected-(U5C-CFOE{slash}NRD-Pad69)") (class "Default")
      (node (ref "U5") (pin "69") (pinfunction "CFOE/NRD_69") (pintype "passive"))
    )
    (net (code "158") (name "unconnected-(U5C-CFWE{slash}NWE{slash}NWRD0-Pad70)") (class "Default")
      (node (ref "U5") (pin "70") (pinfunction "CFWE/NWE/NWRD0_70") (pintype "passive"))
    )
    (net (code "159") (name "unconnected-(U5C-NCS0-Pad68)") (class "Default")
      (node (ref "U5") (pin "68") (pinfunction "NCS0_68") (pintype "passive"))
    )
    (net (code "160") (name "unconnected-(U5C-NWR1{slash}NBS2{slash}A1-Pad98)") (class "Default")
      (node (ref "U5") (pin "98") (pinfunction "NWR1/NBS2/A1_98") (pintype "passive"))
    )
    (net (code "161") (name "unconnected-(U5C-PC4{slash}A23{slash}SPI1_NPCS2-Pad62)") (class "Default")
      (node (ref "U5") (pin "62") (pinfunction "PC4/A23/SPI1_NPCS2_62") (pintype "passive"))
    )
    (net (code "162") (name "unconnected-(U5C-PC5{slash}A24{slash}SPI_NPCS1-Pad67)") (class "Default")
      (node (ref "U5") (pin "67") (pinfunction "PC5/A24/SPI_NPCS1_67") (pintype "passive"))
    )
    (net (code "163") (name "unconnected-(U5C-PC8{slash}NCS4{slash}CFCS0{slash}RTS3-Pad61)") (class "Default")
      (node (ref "U5") (pin "61") (pinfunction "PC8/NCS4/CFCS0/RTS3_61") (pintype "passive"))
    )
    (net (code "164") (name "unconnected-(U5C-PC17{slash}D17{slash}SPI0_NPCS3-Pad129)") (class "Default")
      (node (ref "U5") (pin "129") (pinfunction "PC17/D17/SPI0_NPCS3_129") (pintype "passive"))
    )
    (net (code "165") (name "unconnected-(U5C-PC18{slash}D18{slash}SPI1_NPCS1-Pad130)") (class "Default")
      (node (ref "U5") (pin "130") (pinfunction "PC18/D18/SPI1_NPCS1_130") (pintype "passive"))
    )
    (net (code "166") (name "unconnected-(U5C-PC19{slash}D19{slash}SPI1_NPCS2-Pad131)") (class "Default")
      (node (ref "U5") (pin "131") (pinfunction "PC19/D19/SPI1_NPCS2_131") (pintype "passive"))
    )
    (net (code "167") (name "unconnected-(U5C-PC20{slash}D20{slash}SPI1_NPCS3-Pad134)") (class "Default")
      (node (ref "U5") (pin "134") (pinfunction "PC20/D20/SPI1_NPCS3_134") (pintype "passive"))
    )
    (net (code "168") (name "unconnected-(U5C-PC21{slash}D21{slash}EF100-Pad135)") (class "Default")
      (node (ref "U5") (pin "135") (pinfunction "PC21/D21/EF100_135") (pintype "passive"))
    )
    (net (code "169") (name "unconnected-(U5C-PC22{slash}D22{slash}TCLK5-Pad136)") (class "Default")
      (node (ref "U5") (pin "136") (pinfunction "PC22/D22/TCLK5_136") (pintype "passive"))
    )
    (net (code "170") (name "unconnected-(U5C-PC23{slash}D23-Pad137)") (class "Default")
      (node (ref "U5") (pin "137") (pinfunction "PC23/D23_137") (pintype "passive"))
    )
    (net (code "171") (name "unconnected-(U5C-PC24{slash}D24-Pad138)") (class "Default")
      (node (ref "U5") (pin "138") (pinfunction "PC24/D24_138") (pintype "passive"))
    )
    (net (code "172") (name "unconnected-(U5C-PC25{slash}D25-Pad139)") (class "Default")
      (node (ref "U5") (pin "139") (pinfunction "PC25/D25_139") (pintype "passive"))
    )
    (net (code "173") (name "unconnected-(U5C-PC26{slash}D26-Pad140)") (class "Default")
      (node (ref "U5") (pin "140") (pinfunction "PC26/D26_140") (pintype "passive"))
    )
    (net (code "174") (name "unconnected-(U5C-PC27{slash}D27-Pad141)") (class "Default")
      (node (ref "U5") (pin "141") (pinfunction "PC27/D27_141") (pintype "passive"))
    )
    (net (code "175") (name "unconnected-(U5C-PC28{slash}D28-Pad142)") (class "Default")
      (node (ref "U5") (pin "142") (pinfunction "PC28/D28_142") (pintype "passive"))
    )
    (net (code "176") (name "unconnected-(U5C-PC29{slash}D29-Pad143)") (class "Default")
      (node (ref "U5") (pin "143") (pinfunction "PC29/D29_143") (pintype "passive"))
    )
    (net (code "177") (name "unconnected-(U5C-PC30{slash}D30-Pad144)") (class "Default")
      (node (ref "U5") (pin "144") (pinfunction "PC30/D30_144") (pintype "passive"))
    )
    (net (code "178") (name "unconnected-(U5C-PC31{slash}D31-Pad145)") (class "Default")
      (node (ref "U5") (pin "145") (pinfunction "PC31/D31_145") (pintype "passive"))
    )
    (net (code "179") (name "unconnected-(U6-NC-Pad1)") (class "Default")
      (node (ref "U6") (pin "1") (pinfunction "NC_1") (pintype "passive+no_connect"))
    )
    (net (code "180") (name "unconnected-(U6-NC-Pad2)") (class "Default")
      (node (ref "U6") (pin "2") (pinfunction "NC_2") (pintype "passive+no_connect"))
    )
    (net (code "181") (name "unconnected-(U6-NC-Pad3)") (class "Default")
      (node (ref "U6") (pin "3") (pinfunction "NC_3") (pintype "passive+no_connect"))
    )
    (net (code "182") (name "unconnected-(U6-NC-Pad4)") (class "Default")
      (node (ref "U6") (pin "4") (pinfunction "NC_4") (pintype "passive+no_connect"))
    )
    (net (code "183") (name "unconnected-(U6-NC-Pad5)") (class "Default")
      (node (ref "U6") (pin "5") (pinfunction "NC_5") (pintype "passive+no_connect"))
    )
    (net (code "184") (name "unconnected-(U6-NC-Pad6)") (class "Default")
      (node (ref "U6") (pin "6") (pinfunction "NC_6") (pintype "passive+no_connect"))
    )
    (net (code "185") (name "unconnected-(U6-NC-Pad10)") (class "Default")
      (node (ref "U6") (pin "10") (pinfunction "NC_10") (pintype "passive+no_connect"))
    )
    (net (code "186") (name "unconnected-(U6-NC-Pad11)") (class "Default")
      (node (ref "U6") (pin "11") (pinfunction "NC_11") (pintype "passive+no_connect"))
    )
    (net (code "187") (name "unconnected-(U6-NC-Pad14)") (class "Default")
      (node (ref "U6") (pin "14") (pinfunction "NC_14") (pintype "passive+no_connect"))
    )
    (net (code "188") (name "unconnected-(U6-NC-Pad15)") (class "Default")
      (node (ref "U6") (pin "15") (pinfunction "NC_15") (pintype "passive+no_connect"))
    )
    (net (code "189") (name "unconnected-(U6-NC-Pad20)") (class "Default")
      (node (ref "U6") (pin "20") (pinfunction "NC_20") (pintype "passive+no_connect"))
    )
    (net (code "190") (name "unconnected-(U6-NC-Pad21)") (class "Default")
      (node (ref "U6") (pin "21") (pinfunction "NC_21") (pintype "passive+no_connect"))
    )
    (net (code "191") (name "unconnected-(U6-NC-Pad22)") (class "Default")
      (node (ref "U6") (pin "22") (pinfunction "NC_22") (pintype "passive+no_connect"))
    )
    (net (code "192") (name "unconnected-(U6-NC-Pad23)") (class "Default")
      (node (ref "U6") (pin "23") (pinfunction "NC_23") (pintype "passive+no_connect"))
    )
    (net (code "193") (name "unconnected-(U6-NC-Pad24)") (class "Default")
      (node (ref "U6") (pin "24") (pinfunction "NC_24") (pintype "passive+no_connect"))
    )
    (net (code "194") (name "unconnected-(U6-NC-Pad25)") (class "Default")
      (node (ref "U6") (pin "25") (pinfunction "NC_25") (pintype "passive+no_connect"))
    )
    (net (code "195") (name "unconnected-(U6-NC-Pad26)") (class "Default")
      (node (ref "U6") (pin "26") (pinfunction "NC_26") (pintype "passive+no_connect"))
    )
    (net (code "196") (name "unconnected-(U6-NC-Pad27)") (class "Default")
      (node (ref "U6") (pin "27") (pinfunction "NC_27") (pintype "passive+no_connect"))
    )
    (net (code "197") (name "unconnected-(U6-NC-Pad28)") (class "Default")
      (node (ref "U6") (pin "28") (pinfunction "NC_28") (pintype "passive+no_connect"))
    )
    (net (code "198") (name "unconnected-(U6-NC-Pad33)") (class "Default")
      (node (ref "U6") (pin "33") (pinfunction "NC_33") (pintype "passive+no_connect"))
    )
    (net (code "199") (name "unconnected-(U6-NC-Pad34)") (class "Default")
      (node (ref "U6") (pin "34") (pinfunction "NC_34") (pintype "passive+no_connect"))
    )
    (net (code "200") (name "unconnected-(U6-NC-Pad35)") (class "Default")
      (node (ref "U6") (pin "35") (pinfunction "NC_35") (pintype "passive+no_connect"))
    )
    (net (code "201") (name "unconnected-(U6-NC-Pad39)") (class "Default")
      (node (ref "U6") (pin "39") (pinfunction "NC_39") (pintype "passive+no_connect"))
    )
    (net (code "202") (name "unconnected-(U6-NC-Pad40)") (class "Default")
      (node (ref "U6") (pin "40") (pinfunction "NC_40") (pintype "passive+no_connect"))
    )
    (net (code "203") (name "unconnected-(U6-NC-Pad45)") (class "Default")
      (node (ref "U6") (pin "45") (pinfunction "NC_45") (pintype "passive+no_connect"))
    )
    (net (code "204") (name "unconnected-(U6-NC-Pad46)") (class "Default")
      (node (ref "U6") (pin "46") (pinfunction "NC_46") (pintype "passive+no_connect"))
    )
    (net (code "205") (name "unconnected-(U6-NC-Pad47)") (class "Default")
      (node (ref "U6") (pin "47") (pinfunction "NC_47") (pintype "passive+no_connect"))
    )
    (net (code "206") (name "unconnected-(U6-NC-Pad48)") (class "Default")
      (node (ref "U6") (pin "48") (pinfunction "NC_48") (pintype "passive+no_connect"))
    )
    (net (code "207") (name "unconnected-(U7-WP-Pad7)") (class "Default")
      (node (ref "U7") (pin "7") (pinfunction "WP_7") (pintype "input+no_connect"))
    )
    (net (code "208") (name "unconnected-(U8-NC-Pad40)") (class "Default")
      (node (ref "U8") (pin "40") (pinfunction "NC_40") (pintype "passive+no_connect"))
    )
  )
)
